# LCD-Input_Module.net
KiCad netlist of a schematic drawn in EAGLE
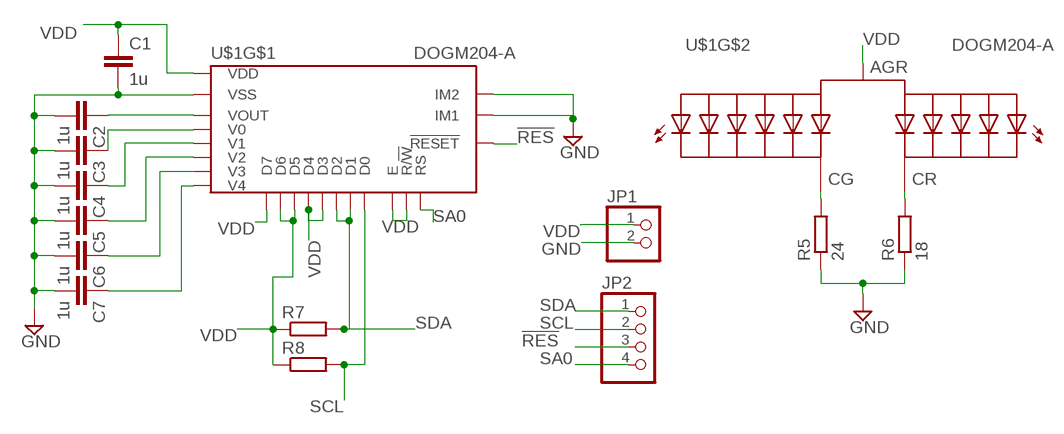
[diagram p0: schematic, sheet 1]
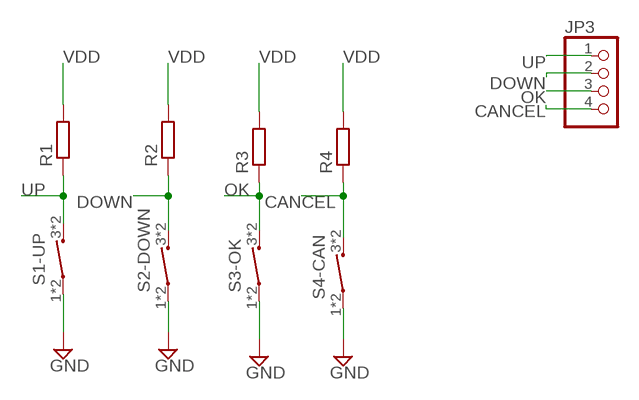
[diagram p1: schematic, sheet 2]

(export (version "E")
  (design (tool "Eeschema 10.0.6"))
  (components
    (comp (ref "C1")
      (value "1u")
      (footprint "eagle-import:C0603")
      (libsource (lib "eagle-import") (part "C-EUC0603"))
    )
    (comp (ref "C2")
      (value "1u")
      (footprint "eagle-import:C0603")
      (libsource (lib "eagle-import") (part "C-EUC0603"))
    )
    (comp (ref "C3")
      (value "1u")
      (footprint "eagle-import:C0603")
      (libsource (lib "eagle-import") (part "C-EUC0603"))
    )
    (comp (ref "C4")
      (value "1u")
      (footprint "eagle-import:C0603")
      (libsource (lib "eagle-import") (part "C-EUC0603"))
    )
    (comp (ref "C5")
      (value "1u")
      (footprint "eagle-import:C0603")
      (libsource (lib "eagle-import") (part "C-EUC0603"))
    )
    (comp (ref "C6")
      (value "1u")
      (footprint "eagle-import:C0603")
      (libsource (lib "eagle-import") (part "C-EUC0603"))
    )
    (comp (ref "C7")
      (value "1u")
      (footprint "eagle-import:C0603")
      (libsource (lib "eagle-import") (part "C-EUC0603"))
    )
    (comp (ref "JP1")
      (value "PINHD-1X2")
      (footprint "eagle-import:1X02")
      (libsource (lib "eagle-import") (part "PINHD-1X2"))
    )
    (comp (ref "JP2")
      (value "PINHD-1X4")
      (footprint "eagle-import:1X04")
      (libsource (lib "eagle-import") (part "PINHD-1X4"))
    )
    (comp (ref "R5")
      (value "24")
      (footprint "eagle-import:R0603")
      (libsource (lib "eagle-import") (part "R-EU_R0603"))
    )
    (comp (ref "R6")
      (value "18")
      (footprint "eagle-import:R0603")
      (libsource (lib "eagle-import") (part "R-EU_R0603"))
    )
    (comp (ref "R7")
      (value "R-EU_R0603")
      (footprint "eagle-import:R0603")
      (libsource (lib "eagle-import") (part "R-EU_R0603"))
    )
    (comp (ref "R8")
      (value "R-EU_R0603")
      (footprint "eagle-import:R0603")
      (libsource (lib "eagle-import") (part "R-EU_R0603"))
    )
    (comp (ref "U$1")
      (value "DOGM204-A")
      (footprint "eagle-import:LCD")
      (libsource (lib "eagle-import") (part "DOGM204-A"))
    )
    (comp (ref "JP3")
      (value "PINHD-1X4")
      (footprint "eagle-import:1X04")
      (libsource (lib "eagle-import") (part "PINHD-1X4"))
    )
    (comp (ref "R1")
      (value "R-EU_R0603")
      (footprint "eagle-import:R0603")
      (libsource (lib "eagle-import") (part "R-EU_R0603"))
    )
    (comp (ref "R2")
      (value "R-EU_R0603")
      (footprint "eagle-import:R0603")
      (libsource (lib "eagle-import") (part "R-EU_R0603"))
    )
    (comp (ref "R3")
      (value "R-EU_R0603")
      (footprint "eagle-import:R0603")
      (libsource (lib "eagle-import") (part "R-EU_R0603"))
    )
    (comp (ref "R4")
      (value "R-EU_R0603")
      (footprint "eagle-import:R0603")
      (libsource (lib "eagle-import") (part "R-EU_R0603"))
    )
    (comp (ref "S1-UP")
      (value "PTS647")
      (footprint "eagle-import:PTS647-TACTSWITCH")
      (libsource (lib "eagle-import") (part "PTS647"))
    )
    (comp (ref "S2-DOWN")
      (value "PTS647")
      (footprint "eagle-import:PTS647-TACTSWITCH")
      (libsource (lib "eagle-import") (part "PTS647"))
    )
    (comp (ref "S3-OK")
      (value "PTS647")
      (footprint "eagle-import:PTS647-TACTSWITCH")
      (libsource (lib "eagle-import") (part "PTS647"))
    )
    (comp (ref "S4-CAN")
      (value "PTS647")
      (footprint "eagle-import:PTS647-TACTSWITCH")
      (libsource (lib "eagle-import") (part "PTS647"))
    )
  )
  (nets
    (net (code "1") (name "CANCEL") (class "Default")
      (node (ref "JP3") (pin "4") (pinfunction "4_4") (pintype "passive"))
      (node (ref "R4") (pin "1") (pinfunction "1_1") (pintype "passive"))
      (node (ref "S4-CAN") (pin "3") (pinfunction "2_3") (pintype "passive"))
      (node (ref "S4-CAN") (pin "4") (pinfunction "2_4") (pintype "passive"))
    )
    (net (code "2") (name "DOWN") (class "Default")
      (node (ref "JP3") (pin "2") (pinfunction "2_2") (pintype "passive"))
      (node (ref "R2") (pin "1") (pinfunction "1_1") (pintype "passive"))
      (node (ref "S2-DOWN") (pin "3") (pinfunction "2_3") (pintype "passive"))
      (node (ref "S2-DOWN") (pin "4") (pinfunction "2_4") (pintype "passive"))
    )
    (net (code "3") (name "GND") (class "Default")
      (node (ref "C1") (pin "2") (pinfunction "2_2") (pintype "passive"))
      (node (ref "C2") (pin "2") (pinfunction "2_2") (pintype "passive"))
      (node (ref "C3") (pin "2") (pinfunction "2_2") (pintype "passive"))
      (node (ref "C4") (pin "2") (pinfunction "2_2") (pintype "passive"))
      (node (ref "C5") (pin "2") (pinfunction "2_2") (pintype "passive"))
      (node (ref "C6") (pin "2") (pinfunction "2_2") (pintype "passive"))
      (node (ref "C7") (pin "2") (pinfunction "2_2") (pintype "passive"))
      (node (ref "JP1") (pin "2") (pinfunction "2_2") (pintype "passive"))
      (node (ref "R5") (pin "1") (pinfunction "1_1") (pintype "passive"))
      (node (ref "R6") (pin "1") (pinfunction "1_1") (pintype "passive"))
      (node (ref "S1-UP") (pin "1") (pinfunction "1_1") (pintype "passive"))
      (node (ref "S1-UP") (pin "2") (pinfunction "1_2") (pintype "passive"))
      (node (ref "S2-DOWN") (pin "1") (pinfunction "1_1") (pintype "passive"))
      (node (ref "S2-DOWN") (pin "2") (pinfunction "1_2") (pintype "passive"))
      (node (ref "S3-OK") (pin "1") (pinfunction "1_1") (pintype "passive"))
      (node (ref "S3-OK") (pin "2") (pinfunction "1_2") (pintype "passive"))
      (node (ref "S4-CAN") (pin "1") (pinfunction "1_1") (pintype "passive"))
      (node (ref "S4-CAN") (pin "2") (pinfunction "1_2") (pintype "passive"))
      (node (ref "U$1") (pin "P$29") (pinfunction "IM2_P$29") (pintype "bidirectional"))
      (node (ref "U$1") (pin "P$30") (pinfunction "IM1_P$30") (pintype "bidirectional"))
      (node (ref "U$1") (pin "P$32") (pinfunction "VSS_P$32") (pintype "bidirectional"))
    )
    (net (code "4") (name "Net-(U$1A-V0)") (class "Default")
      (node (ref "C3") (pin "1") (pinfunction "1_1") (pintype "passive"))
      (node (ref "U$1") (pin "P$24") (pinfunction "V0_P$24") (pintype "bidirectional"))
    )
    (net (code "5") (name "Net-(U$1A-V1)") (class "Default")
      (node (ref "C4") (pin "1") (pinfunction "1_1") (pintype "passive"))
      (node (ref "U$1") (pin "P$25") (pinfunction "V1_P$25") (pintype "bidirectional"))
    )
    (net (code "6") (name "Net-(U$1A-V2)") (class "Default")
      (node (ref "C5") (pin "1") (pinfunction "1_1") (pintype "passive"))
      (node (ref "U$1") (pin "P$26") (pinfunction "V2_P$26") (pintype "bidirectional"))
    )
    (net (code "7") (name "Net-(U$1A-V3)") (class "Default")
      (node (ref "C6") (pin "1") (pinfunction "1_1") (pintype "passive"))
      (node (ref "U$1") (pin "P$27") (pinfunction "V3_P$27") (pintype "bidirectional"))
    )
    (net (code "8") (name "Net-(U$1A-V4)") (class "Default")
      (node (ref "C7") (pin "1") (pinfunction "1_1") (pintype "passive"))
      (node (ref "U$1") (pin "P$28") (pinfunction "V4_P$28") (pintype "bidirectional"))
    )
    (net (code "9") (name "Net-(U$1A-VOUT)") (class "Default")
      (node (ref "C2") (pin "1") (pinfunction "1_1") (pintype "passive"))
      (node (ref "U$1") (pin "P$23") (pinfunction "VOUT_P$23") (pintype "bidirectional"))
    )
    (net (code "10") (name "Net-(U$1B-CG)") (class "Default")
      (node (ref "R5") (pin "2") (pinfunction "2_2") (pintype "passive"))
      (node (ref "U$1") (pin "P$21") (pinfunction "CG_P$21") (pintype "passive"))
    )
    (net (code "11") (name "Net-(U$1B-CR)") (class "Default")
      (node (ref "R6") (pin "2") (pinfunction "2_2") (pintype "passive"))
      (node (ref "U$1") (pin "P$22") (pinfunction "CR_P$22") (pintype "passive"))
    )
    (net (code "12") (name "OK") (class "Default")
      (node (ref "JP3") (pin "3") (pinfunction "3_3") (pintype "passive"))
      (node (ref "R3") (pin "1") (pinfunction "1_1") (pintype "passive"))
      (node (ref "S3-OK") (pin "3") (pinfunction "2_3") (pintype "passive"))
      (node (ref "S3-OK") (pin "4") (pinfunction "2_4") (pintype "passive"))
    )
    (net (code "13") (name "SA0") (class "Default")
      (node (ref "JP2") (pin "4") (pinfunction "4_4") (pintype "passive"))
      (node (ref "U$1") (pin "P$43") (pinfunction "RS_P$43") (pintype "bidirectional"))
    )
    (net (code "14") (name "SCL") (class "Default")
      (node (ref "JP2") (pin "2") (pinfunction "2_2") (pintype "passive"))
      (node (ref "R8") (pin "2") (pinfunction "2_2") (pintype "passive"))
      (node (ref "U$1") (pin "P$40") (pinfunction "D0_P$40") (pintype "bidirectional"))
    )
    (net (code "15") (name "SDA") (class "Default")
      (node (ref "JP2") (pin "1") (pinfunction "1_1") (pintype "passive"))
      (node (ref "R7") (pin "2") (pinfunction "2_2") (pintype "passive"))
      (node (ref "U$1") (pin "P$38") (pinfunction "D2_P$38") (pintype "bidirectional"))
      (node (ref "U$1") (pin "P$39") (pinfunction "D1_P$39") (pintype "bidirectional"))
    )
    (net (code "16") (name "UP") (class "Default")
      (node (ref "JP3") (pin "1") (pinfunction "1_1") (pintype "passive"))
      (node (ref "R1") (pin "1") (pinfunction "1_1") (pintype "passive"))
      (node (ref "S1-UP") (pin "3") (pinfunction "2_3") (pintype "passive"))
      (node (ref "S1-UP") (pin "4") (pinfunction "2_4") (pintype "passive"))
    )
    (net (code "17") (name "VDD") (class "Default")
      (node (ref "C1") (pin "1") (pinfunction "1_1") (pintype "passive"))
      (node (ref "JP1") (pin "1") (pinfunction "1_1") (pintype "passive"))
      (node (ref "R1") (pin "2") (pinfunction "2_2") (pintype "passive"))
      (node (ref "R2") (pin "2") (pinfunction "2_2") (pintype "passive"))
      (node (ref "R3") (pin "2") (pinfunction "2_2") (pintype "passive"))
      (node (ref "R4") (pin "2") (pinfunction "2_2") (pintype "passive"))
      (node (ref "R7") (pin "1") (pinfunction "1_1") (pintype "passive"))
      (node (ref "R8") (pin "1") (pinfunction "1_1") (pintype "passive"))
      (node (ref "U$1") (pin "P$1") (pinfunction "AGR_P$1") (pintype "passive"))
      (node (ref "U$1") (pin "P$31") (pinfunction "VDD_P$31") (pintype "bidirectional"))
      (node (ref "U$1") (pin "P$33") (pinfunction "D7_P$33") (pintype "bidirectional"))
      (node (ref "U$1") (pin "P$34") (pinfunction "D6_P$34") (pintype "bidirectional"))
      (node (ref "U$1") (pin "P$35") (pinfunction "D5_P$35") (pintype "bidirectional"))
      (node (ref "U$1") (pin "P$36") (pinfunction "D4_P$36") (pintype "bidirectional"))
      (node (ref "U$1") (pin "P$37") (pinfunction "D3_P$37") (pintype "bidirectional"))
      (node (ref "U$1") (pin "P$41") (pinfunction "E_P$41") (pintype "bidirectional"))
      (node (ref "U$1") (pin "P$42") (pinfunction "R/~{W}_P$42") (pintype "bidirectional"))
    )
    (net (code "18") (name "~{RES}") (class "Default")
      (node (ref "JP2") (pin "3") (pinfunction "3_3") (pintype "passive"))
      (node (ref "U$1") (pin "P$44") (pinfunction "~{RESET}_P$44") (pintype "bidirectional"))
    )
  )
)
